# Split-ADA4304-4.net
KiCad netlist of a schematic drawn in EAGLE
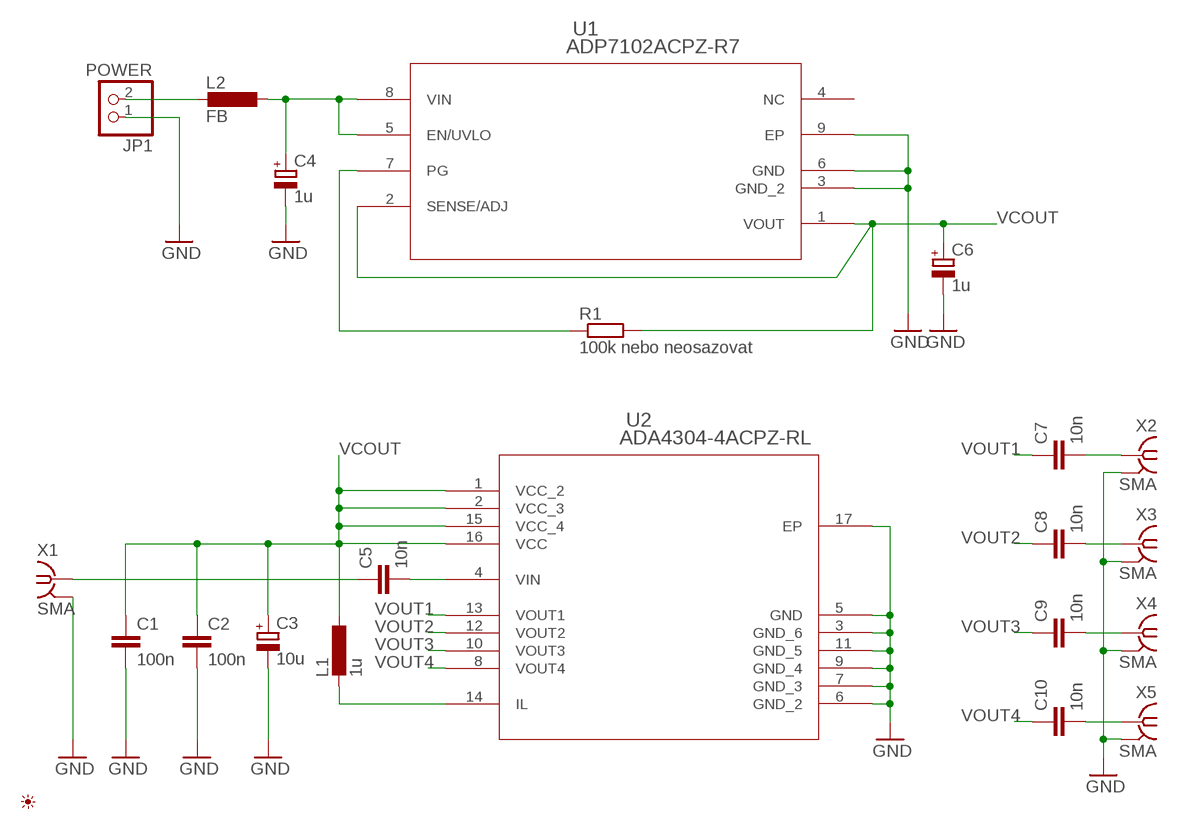
[diagram p0: schematic, sheet 1]

(export (version "E")
  (design (tool "Eeschema 10.0.6"))
  (components
    (comp (ref "C1")
      (value "100n")
      (footprint "eagle-import:C0603")
      (libsource (lib "eagle-import") (part "C-EUC0603"))
    )
    (comp (ref "C2")
      (value "100n")
      (footprint "eagle-import:C0603")
      (libsource (lib "eagle-import") (part "C-EUC0603"))
    )
    (comp (ref "C3")
      (value "10u")
      (footprint "eagle-import:SMC_A")
      (libsource (lib "eagle-import") (part "CPOL-EUSMCA"))
    )
    (comp (ref "C4")
      (value "1u")
      (footprint "eagle-import:SMC_A")
      (libsource (lib "eagle-import") (part "CPOL-EUSMCA"))
    )
    (comp (ref "C5")
      (value "10n")
      (footprint "eagle-import:C0603")
      (libsource (lib "eagle-import") (part "C-EUC0603"))
    )
    (comp (ref "C6")
      (value "1u")
      (footprint "eagle-import:SMC_A")
      (libsource (lib "eagle-import") (part "CPOL-EUSMCA"))
    )
    (comp (ref "C7")
      (value "10n")
      (footprint "eagle-import:C0603")
      (libsource (lib "eagle-import") (part "C-EUC0603"))
    )
    (comp (ref "C8")
      (value "10n")
      (footprint "eagle-import:C0603")
      (libsource (lib "eagle-import") (part "C-EUC0603"))
    )
    (comp (ref "C9")
      (value "10n")
      (footprint "eagle-import:C0603")
      (libsource (lib "eagle-import") (part "C-EUC0603"))
    )
    (comp (ref "C10")
      (value "10n")
      (footprint "eagle-import:C0603")
      (libsource (lib "eagle-import") (part "C-EUC0603"))
    )
    (comp (ref "JP1")
      (value "POWER")
      (footprint "eagle-import:1X02")
      (libsource (lib "eagle-import") (part "PINHD-1X2"))
    )
    (comp (ref "L1")
      (value "1u")
      (footprint "eagle-import:L2012C")
      (libsource (lib "eagle-import") (part "L-EUL2012C"))
    )
    (comp (ref "L2")
      (value "FB")
      (footprint "eagle-import:L2012C")
      (libsource (lib "eagle-import") (part "L-EUL2012C"))
    )
    (comp (ref "PICTO1")
      (value "PICTO_1")
      (footprint "eagle-import:PICTO_1")
      (libsource (lib "eagle-import") (part "PICTO_1"))
    )
    (comp (ref "R1")
      (value "100k nebo neosazovat")
      (footprint "eagle-import:R0603")
      (libsource (lib "eagle-import") (part "R-EU_R0603"))
    )
    (comp (ref "U1")
      (value "ADP7102ACPZ-R7")
      (footprint "eagle-import:CP_8_5")
      (libsource (lib "eagle-import") (part "ADP7102ACPZ-R7"))
    )
    (comp (ref "U2")
      (value "ADA4304-4ACPZ-RL")
      (footprint "eagle-import:CP_16_2")
      (libsource (lib "eagle-import") (part "ADA4304-4ACPZ-RL"))
    )
    (comp (ref "X1")
      (value "SMA")
      (footprint "eagle-import:J502-ND-142-0701-801_806")
      (fields (field (name "MF") "JOHNSON COMPONENTS") (field (name "MPN") "142-0701-801"))
      (libsource (lib "eagle-import") (part "SMA-142-0701-801/806"))
    )
    (comp (ref "X2")
      (value "SMA")
      (footprint "eagle-import:J502-ND-142-0701-801_806")
      (fields (field (name "MF") "JOHNSON COMPONENTS") (field (name "MPN") "142-0701-801"))
      (libsource (lib "eagle-import") (part "SMA-142-0701-801/806"))
    )
    (comp (ref "X3")
      (value "SMA")
      (footprint "eagle-import:J502-ND-142-0701-801_806")
      (fields (field (name "MF") "JOHNSON COMPONENTS") (field (name "MPN") "142-0701-801"))
      (libsource (lib "eagle-import") (part "SMA-142-0701-801/806"))
    )
    (comp (ref "X4")
      (value "SMA")
      (footprint "eagle-import:J502-ND-142-0701-801_806")
      (fields (field (name "MF") "JOHNSON COMPONENTS") (field (name "MPN") "142-0701-801"))
      (libsource (lib "eagle-import") (part "SMA-142-0701-801/806"))
    )
    (comp (ref "X5")
      (value "SMA")
      (footprint "eagle-import:J502-ND-142-0701-801_806")
      (fields (field (name "MF") "JOHNSON COMPONENTS") (field (name "MPN") "142-0701-801"))
      (libsource (lib "eagle-import") (part "SMA-142-0701-801/806"))
    )
  )
  (nets
    (net (code "1") (name "/VCOUT") (class "Default")
      (node (ref "C1") (pin "1") (pinfunction "1_1") (pintype "passive"))
      (node (ref "C2") (pin "1") (pinfunction "1_1") (pintype "passive"))
      (node (ref "C3") (pin "+") (pinfunction "+_+") (pintype "passive"))
      (node (ref "C6") (pin "+") (pinfunction "+_+") (pintype "passive"))
      (node (ref "L1") (pin "1") (pinfunction "1_1") (pintype "passive"))
      (node (ref "R1") (pin "2") (pinfunction "2_2") (pintype "passive"))
      (node (ref "U1") (pin "1") (pinfunction "VOUT_1") (pintype "passive"))
      (node (ref "U1") (pin "2") (pinfunction "SENSE/ADJ_2") (pintype "passive"))
      (node (ref "U2") (pin "1") (pinfunction "VCC_2_1") (pintype "power_in"))
      (node (ref "U2") (pin "15") (pinfunction "VCC_4_15") (pintype "power_in"))
      (node (ref "U2") (pin "16") (pinfunction "VCC_16") (pintype "power_in"))
      (node (ref "U2") (pin "2") (pinfunction "VCC_3_2") (pintype "power_in"))
    )
    (net (code "2") (name "/VOUT1") (class "Default")
      (node (ref "C7") (pin "1") (pinfunction "1_1") (pintype "passive"))
      (node (ref "U2") (pin "13") (pinfunction "VOUT1_13") (pintype "output"))
    )
    (net (code "3") (name "/VOUT2") (class "Default")
      (node (ref "C8") (pin "1") (pinfunction "1_1") (pintype "passive"))
      (node (ref "U2") (pin "12") (pinfunction "VOUT2_12") (pintype "output"))
    )
    (net (code "4") (name "/VOUT3") (class "Default")
      (node (ref "C9") (pin "1") (pinfunction "1_1") (pintype "passive"))
      (node (ref "U2") (pin "10") (pinfunction "VOUT3_10") (pintype "output"))
    )
    (net (code "5") (name "/VOUT4") (class "Default")
      (node (ref "C10") (pin "1") (pinfunction "1_1") (pintype "passive"))
      (node (ref "U2") (pin "8") (pinfunction "VOUT4_8") (pintype "output"))
    )
    (net (code "6") (name "GND") (class "Default")
      (node (ref "C1") (pin "2") (pinfunction "2_2") (pintype "passive"))
      (node (ref "C2") (pin "2") (pinfunction "2_2") (pintype "passive"))
      (node (ref "C3") (pin "-") (pinfunction "-_-") (pintype "passive"))
      (node (ref "C4") (pin "-") (pinfunction "-_-") (pintype "passive"))
      (node (ref "C6") (pin "-") (pinfunction "-_-") (pintype "passive"))
      (node (ref "JP1") (pin "1") (pinfunction "1_1") (pintype "passive"))
      (node (ref "U1") (pin "3") (pinfunction "GND_2_3") (pintype "passive"))
      (node (ref "U1") (pin "6") (pinfunction "GND_6") (pintype "passive"))
      (node (ref "U1") (pin "9") (pinfunction "EP_9") (pintype "passive"))
      (node (ref "U2") (pin "11") (pinfunction "GND_5_11") (pintype "passive"))
      (node (ref "U2") (pin "17") (pinfunction "EP_17") (pintype "passive"))
      (node (ref "U2") (pin "3") (pinfunction "GND_6_3") (pintype "passive"))
      (node (ref "U2") (pin "5") (pinfunction "GND_5") (pintype "passive"))
      (node (ref "U2") (pin "6") (pinfunction "GND_2_6") (pintype "passive"))
      (node (ref "U2") (pin "7") (pinfunction "GND_3_7") (pintype "passive"))
      (node (ref "U2") (pin "9") (pinfunction "GND_4_9") (pintype "passive"))
      (node (ref "X1") (pin "G@1") (pinfunction "2_G@1") (pintype "passive"))
      (node (ref "X1") (pin "G@2") (pinfunction "2_G@2") (pintype "passive"))
      (node (ref "X1") (pin "G@3") (pinfunction "2_G@3") (pintype "passive"))
      (node (ref "X1") (pin "G@4") (pinfunction "2_G@4") (pintype "passive"))
      (node (ref "X2") (pin "G@1") (pinfunction "2_G@1") (pintype "passive"))
      (node (ref "X2") (pin "G@2") (pinfunction "2_G@2") (pintype "passive"))
      (node (ref "X2") (pin "G@3") (pinfunction "2_G@3") (pintype "passive"))
      (node (ref "X2") (pin "G@4") (pinfunction "2_G@4") (pintype "passive"))
      (node (ref "X3") (pin "G@1") (pinfunction "2_G@1") (pintype "passive"))
      (node (ref "X3") (pin "G@2") (pinfunction "2_G@2") (pintype "passive"))
      (node (ref "X3") (pin "G@3") (pinfunction "2_G@3") (pintype "passive"))
      (node (ref "X3") (pin "G@4") (pinfunction "2_G@4") (pintype "passive"))
      (node (ref "X4") (pin "G@1") (pinfunction "2_G@1") (pintype "passive"))
      (node (ref "X4") (pin "G@2") (pinfunction "2_G@2") (pintype "passive"))
      (node (ref "X4") (pin "G@3") (pinfunction "2_G@3") (pintype "passive"))
      (node (ref "X4") (pin "G@4") (pinfunction "2_G@4") (pintype "passive"))
      (node (ref "X5") (pin "G@1") (pinfunction "2_G@1") (pintype "passive"))
      (node (ref "X5") (pin "G@2") (pinfunction "2_G@2") (pintype "passive"))
      (node (ref "X5") (pin "G@3") (pinfunction "2_G@3") (pintype "passive"))
      (node (ref "X5") (pin "G@4") (pinfunction "2_G@4") (pintype "passive"))
    )
    (net (code "7") (name "Net-(C5-Pad1)") (class "Default")
      (node (ref "C5") (pin "1") (pinfunction "1_1") (pintype "passive"))
      (node (ref "X1") (pin "1") (pinfunction "1_1") (pintype "passive"))
    )
    (net (code "8") (name "Net-(C7-Pad2)") (class "Default")
      (node (ref "C7") (pin "2") (pinfunction "2_2") (pintype "passive"))
      (node (ref "X2") (pin "1") (pinfunction "1_1") (pintype "passive"))
    )
    (net (code "9") (name "Net-(C8-Pad2)") (class "Default")
      (node (ref "C8") (pin "2") (pinfunction "2_2") (pintype "passive"))
      (node (ref "X3") (pin "1") (pinfunction "1_1") (pintype "passive"))
    )
    (net (code "10") (name "Net-(C9-Pad2)") (class "Default")
      (node (ref "C9") (pin "2") (pinfunction "2_2") (pintype "passive"))
      (node (ref "X4") (pin "1") (pinfunction "1_1") (pintype "passive"))
    )
    (net (code "11") (name "Net-(C10-Pad2)") (class "Default")
      (node (ref "C10") (pin "2") (pinfunction "2_2") (pintype "passive"))
      (node (ref "X5") (pin "1") (pinfunction "1_1") (pintype "passive"))
    )
    (net (code "12") (name "Net-(JP1-Pad2)") (class "Default")
      (node (ref "JP1") (pin "2") (pinfunction "2_2") (pintype "passive"))
      (node (ref "L2") (pin "2") (pinfunction "2_2") (pintype "passive"))
    )
    (net (code "13") (name "Net-(U1-EN{slash}UVLO)") (class "Default")
      (node (ref "C4") (pin "+") (pinfunction "+_+") (pintype "passive"))
      (node (ref "L2") (pin "1") (pinfunction "1_1") (pintype "passive"))
      (node (ref "U1") (pin "5") (pinfunction "EN/UVLO_5") (pintype "passive"))
      (node (ref "U1") (pin "8") (pinfunction "VIN_8") (pintype "passive"))
    )
    (net (code "14") (name "Net-(U1-PG)") (class "Default")
      (node (ref "R1") (pin "1") (pinfunction "1_1") (pintype "passive"))
      (node (ref "U1") (pin "7") (pinfunction "PG_7") (pintype "passive"))
    )
    (net (code "15") (name "Net-(U2-IL)") (class "Default")
      (node (ref "L1") (pin "2") (pinfunction "2_2") (pintype "passive"))
      (node (ref "U2") (pin "14") (pinfunction "IL_14") (pintype "passive"))
    )
    (net (code "16") (name "Net-(U2-VIN)") (class "Default")
      (node (ref "C5") (pin "2") (pinfunction "2_2") (pintype "passive"))
      (node (ref "U2") (pin "4") (pinfunction "VIN_4") (pintype "input"))
    )
    (net (code "17") (name "unconnected-(U1-NC-Pad4)") (class "Default")
      (node (ref "U1") (pin "4") (pinfunction "NC_4") (pintype "passive"))
    )
  )
)
